# inverter.net
KiCad netlist of a schematic drawn in EAGLE
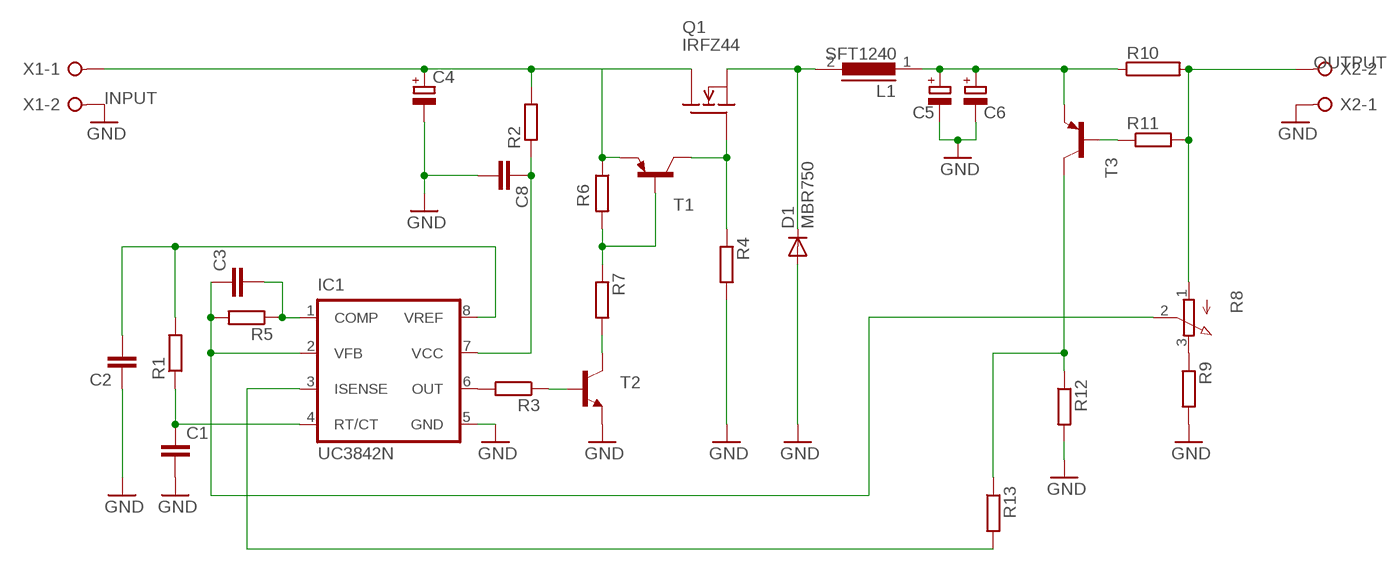
[diagram p0: schematic, sheet 1]

(export (version "E")
  (design (tool "Eeschema 10.0.6"))
  (components
    (comp (ref "C1")
      (value "C-EU050-024X044")
      (footprint "eagle-import:C050-024X044")
      (libsource (lib "eagle-import") (part "C-EU050-024X044"))
    )
    (comp (ref "C2")
      (value "C-EU050-025X075")
      (footprint "eagle-import:C050-025X075")
      (libsource (lib "eagle-import") (part "C-EU050-025X075"))
    )
    (comp (ref "C3")
      (value "C-EU050-024X044")
      (footprint "eagle-import:C050-024X044")
      (libsource (lib "eagle-import") (part "C-EU050-024X044"))
    )
    (comp (ref "C4")
      (value "CPOL-EUE5-8.5")
      (footprint "eagle-import:E5-8,5")
      (libsource (lib "eagle-import") (part "CPOL-EUE5-8.5"))
    )
    (comp (ref "C5")
      (value "CPOL-EUE5-8.5")
      (footprint "eagle-import:E5-8,5")
      (libsource (lib "eagle-import") (part "CPOL-EUE5-8.5"))
    )
    (comp (ref "C6")
      (value "CPOL-EUE5-8.5")
      (footprint "eagle-import:E5-8,5")
      (libsource (lib "eagle-import") (part "CPOL-EUE5-8.5"))
    )
    (comp (ref "C8")
      (value "C-EU050-025X075")
      (footprint "eagle-import:C050-025X075")
      (libsource (lib "eagle-import") (part "C-EU050-025X075"))
    )
    (comp (ref "D1")
      (value "MBR750")
      (footprint "eagle-import:TO220AC")
      (libsource (lib "eagle-import") (part "MBR750"))
    )
    (comp (ref "IC1")
      (value "UC3842N")
      (footprint "eagle-import:DIL08")
      (libsource (lib "eagle-import") (part "UC384N2"))
    )
    (comp (ref "L1")
      (value "SFT1240")
      (footprint "eagle-import:SFT1240")
      (libsource (lib "eagle-import") (part "SFT1240"))
    )
    (comp (ref "Q1")
      (value "IRFZ44")
      (footprint "eagle-import:TO220")
      (libsource (lib "eagle-import") (part "IRF540"))
    )
    (comp (ref "R1")
      (value "R-EU_0207/10")
      (footprint "eagle-import:0207_10")
      (libsource (lib "eagle-import") (part "R-EU_0207/10"))
    )
    (comp (ref "R2")
      (value "R-EU_0207/10")
      (footprint "eagle-import:0207_10")
      (libsource (lib "eagle-import") (part "R-EU_0207/10"))
    )
    (comp (ref "R3")
      (value "R-EU_0207/10")
      (footprint "eagle-import:0207_10")
      (libsource (lib "eagle-import") (part "R-EU_0207/10"))
    )
    (comp (ref "R4")
      (value "R-EU_0207/10")
      (footprint "eagle-import:0207_10")
      (libsource (lib "eagle-import") (part "R-EU_0207/10"))
    )
    (comp (ref "R5")
      (value "R-EU_0207/10")
      (footprint "eagle-import:0207_10")
      (libsource (lib "eagle-import") (part "R-EU_0207/10"))
    )
    (comp (ref "R6")
      (value "R-EU_0207/10")
      (footprint "eagle-import:0207_10")
      (libsource (lib "eagle-import") (part "R-EU_0207/10"))
    )
    (comp (ref "R7")
      (value "R-EU_0207/10")
      (footprint "eagle-import:0207_10")
      (libsource (lib "eagle-import") (part "R-EU_0207/10"))
    )
    (comp (ref "R8")
      (value "3RP/1610N")
      (footprint "eagle-import:3RP_1610N")
      (libsource (lib "eagle-import") (part "3RP/1610N"))
    )
    (comp (ref "R9")
      (value "R-EU_0207/10")
      (footprint "eagle-import:0207_10")
      (libsource (lib "eagle-import") (part "R-EU_0207/10"))
    )
    (comp (ref "R10")
      (value "RKH208-8")
      (footprint "eagle-import:KH208-8")
      (libsource (lib "eagle-import") (part "RKH208-8"))
    )
    (comp (ref "R11")
      (value "R-EU_0207/10")
      (footprint "eagle-import:0207_10")
      (libsource (lib "eagle-import") (part "R-EU_0207/10"))
    )
    (comp (ref "R12")
      (value "R-EU_0207/10")
      (footprint "eagle-import:0207_10")
      (libsource (lib "eagle-import") (part "R-EU_0207/10"))
    )
    (comp (ref "R13")
      (value "R-EU_0207/10")
      (footprint "eagle-import:0207_10")
      (libsource (lib "eagle-import") (part "R-EU_0207/10"))
    )
    (comp (ref "T1")
      (value "BC557A-PNP-TO92-EBC")
      (footprint "eagle-import:TO92-EBC")
      (libsource (lib "eagle-import") (part "-PNP-TO92-EBCBC557A"))
    )
    (comp (ref "T2")
      (value "BC547-NPN-TO92-CBE")
      (footprint "eagle-import:TO92-CBE")
      (libsource (lib "eagle-import") (part "-NPN-TO92-CBEBC547"))
    )
    (comp (ref "T3")
      (value "BC557A-PNP-TO92-EBC")
      (footprint "eagle-import:TO92-EBC")
      (libsource (lib "eagle-import") (part "-PNP-TO92-EBCBC557A"))
    )
    (comp (ref "X1")
      (value "W237-02P")
      (footprint "eagle-import:W237-132")
      (libsource (lib "eagle-import") (part "W237-02P"))
    )
    (comp (ref "X2")
      (value "W237-02P")
      (footprint "eagle-import:W237-132")
      (libsource (lib "eagle-import") (part "W237-02P"))
    )
  )
  (nets
    (net (code "1") (name "GND") (class "Default")
      (node (ref "C1") (pin "2") (pinfunction "2_2") (pintype "passive"))
      (node (ref "C2") (pin "1") (pinfunction "1_1") (pintype "passive"))
      (node (ref "C4") (pin "-") (pinfunction "-_-") (pintype "passive"))
      (node (ref "C5") (pin "-") (pinfunction "-_-") (pintype "passive"))
      (node (ref "C6") (pin "-") (pinfunction "-_-") (pintype "passive"))
      (node (ref "C8") (pin "2") (pinfunction "2_2") (pintype "passive"))
      (node (ref "D1") (pin "A") (pinfunction "A_A") (pintype "passive"))
      (node (ref "IC1") (pin "5") (pinfunction "GND_5") (pintype "power_in"))
      (node (ref "R12") (pin "2") (pinfunction "2_2") (pintype "passive"))
      (node (ref "R4") (pin "2") (pinfunction "2_2") (pintype "passive"))
      (node (ref "R9") (pin "2") (pinfunction "2_2") (pintype "passive"))
      (node (ref "T2") (pin "E") (pinfunction "E_E") (pintype "passive"))
      (node (ref "X1") (pin "2") (pinfunction "KL_2") (pintype "passive"))
      (node (ref "X2") (pin "1") (pinfunction "KL_1") (pintype "passive"))
    )
    (net (code "2") (name "Net-(C5-Pad+)") (class "Default")
      (node (ref "C5") (pin "+") (pinfunction "+_+") (pintype "passive"))
      (node (ref "C6") (pin "+") (pinfunction "+_+") (pintype "passive"))
      (node (ref "L1") (pin "1") (pinfunction "1_1") (pintype "passive"))
      (node (ref "R10") (pin "1") (pinfunction "1_1") (pintype "passive"))
      (node (ref "T3") (pin "E") (pinfunction "E_E") (pintype "passive"))
    )
    (net (code "3") (name "Net-(IC1-COMP)") (class "Default")
      (node (ref "C3") (pin "2") (pinfunction "2_2") (pintype "passive"))
      (node (ref "IC1") (pin "1") (pinfunction "COMP_1") (pintype "passive"))
      (node (ref "R5") (pin "1") (pinfunction "1_1") (pintype "passive"))
    )
    (net (code "4") (name "Net-(IC1-ISENSE)") (class "Default")
      (node (ref "IC1") (pin "3") (pinfunction "ISENSE_3") (pintype "input"))
      (node (ref "R13") (pin "2") (pinfunction "2_2") (pintype "passive"))
    )
    (net (code "5") (name "Net-(IC1-OUT)") (class "Default")
      (node (ref "IC1") (pin "6") (pinfunction "OUT_6") (pintype "output"))
      (node (ref "R3") (pin "2") (pinfunction "2_2") (pintype "passive"))
    )
    (net (code "6") (name "Net-(IC1-RT{slash}CT)") (class "Default")
      (node (ref "C1") (pin "1") (pinfunction "1_1") (pintype "passive"))
      (node (ref "IC1") (pin "4") (pinfunction "RT/CT_4") (pintype "passive"))
      (node (ref "R1") (pin "1") (pinfunction "1_1") (pintype "passive"))
    )
    (net (code "7") (name "Net-(IC1-VCC)") (class "Default")
      (node (ref "C8") (pin "1") (pinfunction "1_1") (pintype "passive"))
      (node (ref "IC1") (pin "7") (pinfunction "VCC_7") (pintype "power_in"))
      (node (ref "R2") (pin "1") (pinfunction "1_1") (pintype "passive"))
    )
    (net (code "8") (name "Net-(IC1-VFB)") (class "Default")
      (node (ref "C3") (pin "1") (pinfunction "1_1") (pintype "passive"))
      (node (ref "IC1") (pin "2") (pinfunction "VFB_2") (pintype "input"))
      (node (ref "R5") (pin "2") (pinfunction "2_2") (pintype "passive"))
      (node (ref "R8") (pin "2") (pinfunction "S_2") (pintype "passive"))
    )
    (net (code "9") (name "Net-(IC1-VREF)") (class "Default")
      (node (ref "C2") (pin "2") (pinfunction "2_2") (pintype "passive"))
      (node (ref "IC1") (pin "8") (pinfunction "VREF_8") (pintype "passive"))
      (node (ref "R1") (pin "2") (pinfunction "2_2") (pintype "passive"))
    )
    (net (code "10") (name "Net-(Q1-D)") (class "Default")
      (node (ref "C4") (pin "+") (pinfunction "+_+") (pintype "passive"))
      (node (ref "Q1") (pin "2") (pinfunction "D_2") (pintype "passive"))
      (node (ref "R2") (pin "2") (pinfunction "2_2") (pintype "passive"))
      (node (ref "R6") (pin "1") (pinfunction "1_1") (pintype "passive"))
      (node (ref "T1") (pin "E") (pinfunction "E_E") (pintype "passive"))
      (node (ref "X1") (pin "1") (pinfunction "KL_1") (pintype "passive"))
    )
    (net (code "11") (name "Net-(Q1-G)") (class "Default")
      (node (ref "Q1") (pin "1") (pinfunction "G_1") (pintype "passive"))
      (node (ref "R4") (pin "1") (pinfunction "1_1") (pintype "passive"))
      (node (ref "T1") (pin "C") (pinfunction "C_C") (pintype "passive"))
    )
    (net (code "12") (name "Net-(Q1-S)") (class "Default")
      (node (ref "D1") (pin "C") (pinfunction "C_C") (pintype "passive"))
      (node (ref "L1") (pin "2") (pinfunction "2_2") (pintype "passive"))
      (node (ref "Q1") (pin "3") (pinfunction "S_3") (pintype "passive"))
    )
    (net (code "13") (name "Net-(R3-Pad1)") (class "Default")
      (node (ref "R3") (pin "1") (pinfunction "1_1") (pintype "passive"))
      (node (ref "T2") (pin "B") (pinfunction "B_B") (pintype "passive"))
    )
    (net (code "14") (name "Net-(R6-Pad2)") (class "Default")
      (node (ref "R6") (pin "2") (pinfunction "2_2") (pintype "passive"))
      (node (ref "R7") (pin "1") (pinfunction "1_1") (pintype "passive"))
      (node (ref "T1") (pin "B") (pinfunction "B_B") (pintype "passive"))
    )
    (net (code "15") (name "Net-(R7-Pad2)") (class "Default")
      (node (ref "R7") (pin "2") (pinfunction "2_2") (pintype "passive"))
      (node (ref "T2") (pin "C") (pinfunction "C_C") (pintype "passive"))
    )
    (net (code "16") (name "Net-(R8-A)") (class "Default")
      (node (ref "R10") (pin "2") (pinfunction "2_2") (pintype "passive"))
      (node (ref "R11") (pin "2") (pinfunction "2_2") (pintype "passive"))
      (node (ref "R8") (pin "1") (pinfunction "A_1") (pintype "passive"))
      (node (ref "X2") (pin "2") (pinfunction "KL_2") (pintype "passive"))
    )
    (net (code "17") (name "Net-(R8-E)") (class "Default")
      (node (ref "R8") (pin "3") (pinfunction "E_3") (pintype "passive"))
      (node (ref "R9") (pin "1") (pinfunction "1_1") (pintype "passive"))
    )
    (net (code "18") (name "Net-(R11-Pad1)") (class "Default")
      (node (ref "R11") (pin "1") (pinfunction "1_1") (pintype "passive"))
      (node (ref "T3") (pin "B") (pinfunction "B_B") (pintype "passive"))
    )
    (net (code "19") (name "Net-(R12-Pad1)") (class "Default")
      (node (ref "R12") (pin "1") (pinfunction "1_1") (pintype "passive"))
      (node (ref "R13") (pin "1") (pinfunction "1_1") (pintype "passive"))
      (node (ref "T3") (pin "C") (pinfunction "C_C") (pintype "passive"))
    )
  )
)
